# minime_2_1_1.net
KiCad netlist of a schematic drawn in EAGLE
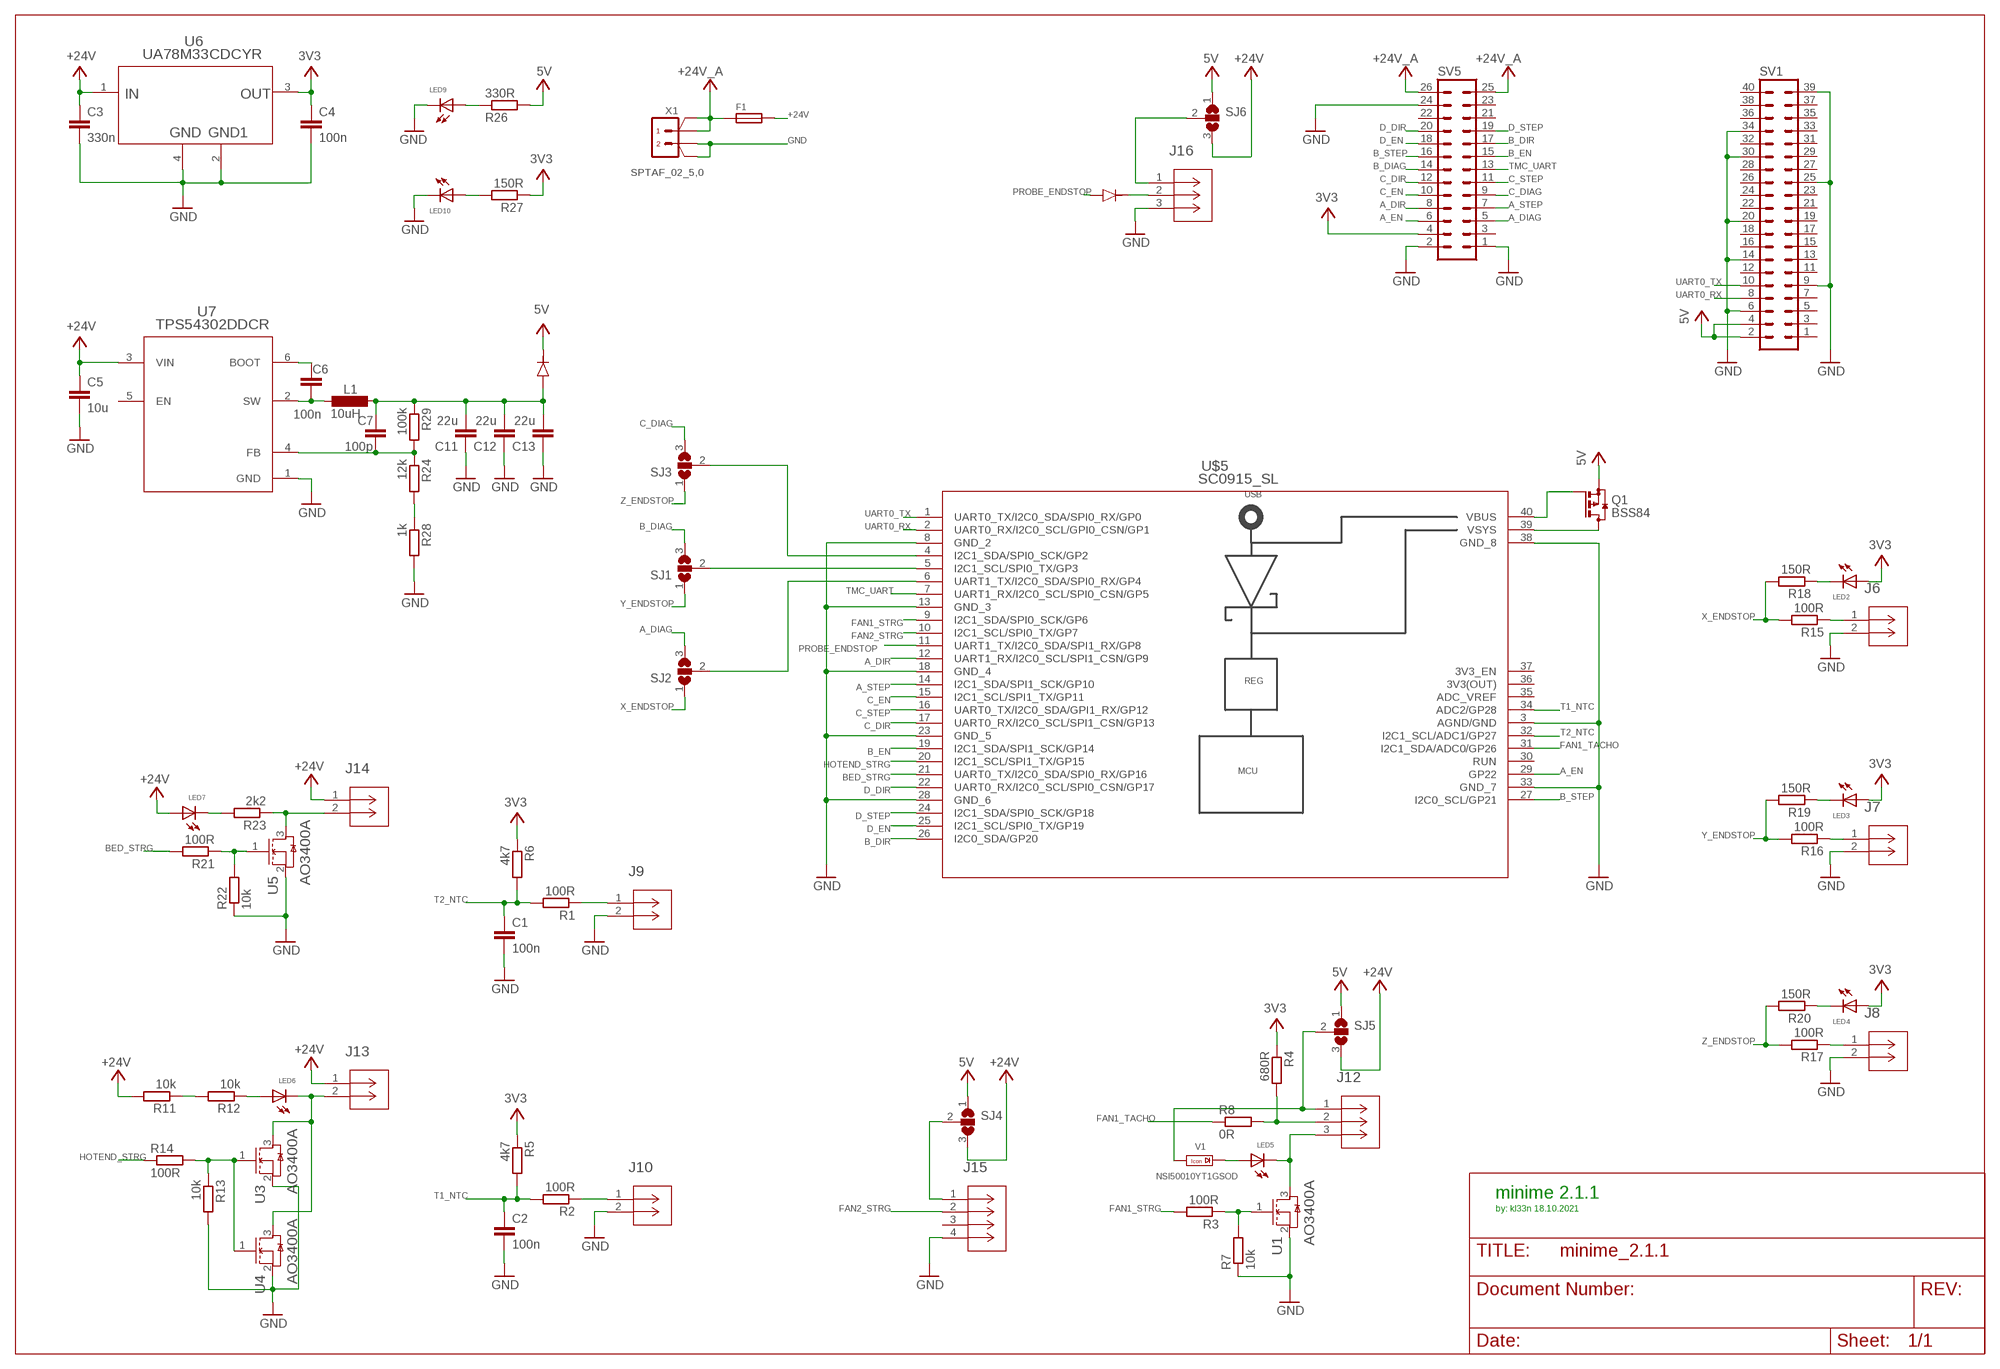
[diagram p0: schematic, sheet 1]

(export (version "E")
  (design (tool "Eeschema 10.0.6"))
  (components
    (comp (ref "C1")
      (value "100n")
      (footprint "eagle-import:C0603")
      (libsource (lib "eagle-import") (part "C-EUC0603"))
    )
    (comp (ref "C2")
      (value "100n")
      (footprint "eagle-import:C0603")
      (libsource (lib "eagle-import") (part "C-EUC0603"))
    )
    (comp (ref "C3")
      (value "330n")
      (footprint "eagle-import:C0603")
      (libsource (lib "eagle-import") (part "C-EUC0603"))
    )
    (comp (ref "C4")
      (value "100n")
      (footprint "eagle-import:C0603")
      (libsource (lib "eagle-import") (part "C-EUC0603"))
    )
    (comp (ref "C5")
      (value "10u")
      (footprint "eagle-import:C0603")
      (libsource (lib "eagle-import") (part "C-EUC0603"))
    )
    (comp (ref "C6")
      (value "100n")
      (footprint "eagle-import:C0603")
      (libsource (lib "eagle-import") (part "C-EUC0603"))
    )
    (comp (ref "C7")
      (value "100p")
      (footprint "eagle-import:C0603")
      (libsource (lib "eagle-import") (part "C-EUC0603"))
    )
    (comp (ref "C11")
      (value "22u")
      (footprint "eagle-import:C1210K")
      (libsource (lib "eagle-import") (part "C-EUC1210K"))
    )
    (comp (ref "C12")
      (value "22u")
      (footprint "eagle-import:C1210K")
      (libsource (lib "eagle-import") (part "C-EUC1210K"))
    )
    (comp (ref "C13")
      (value "22u")
      (footprint "eagle-import:C1210K")
      (libsource (lib "eagle-import") (part "C-EUC1210K"))
    )
    (comp (ref "CR1")
      (value "SS54")
      (footprint "eagle-import:DIODE_DO214AC")
      (fields
        (field (name "MANUFACTURER_PART_NUMBER") "SS14-E3/5AT")
        (field (name "COPYRIGHT") "Copyright (C) 2021 Ultra Librarian. All rights reserved.")
      )
      (libsource (lib "eagle-import") (part "SS14-E3/5AT"))
    )
    (comp (ref "CR2")
      (value "SS14")
      (footprint "eagle-import:DIODE_DO214AC")
      (fields
        (field (name "MANUFACTURER_PART_NUMBER") "SS14-E3/5AT")
        (field (name "COPYRIGHT") "Copyright (C) 2021 Ultra Librarian. All rights reserved.")
      )
      (libsource (lib "eagle-import") (part "SS14-E3/5AT"))
    )
    (comp (ref "F1")
      (value "FUSE/SERIE154")
      (footprint "eagle-import:FUSE_NANO-OMNI")
      (libsource (lib "eagle-import") (part "FUSE/SERIE154"))
    )
    (comp (ref "J6")
      (value "B2B-XH-A(LF)(SN)")
      (footprint "eagle-import:CONN_B2B-XH-A(LF)(SN)_JST")
      (fields (field (name "COPYRIGHT") "Copyright (C) 2018 Accelerated Designs. All rights reserved"))
      (libsource (lib "eagle-import") (part "B2B-XH-A(LF)(SN)"))
    )
    (comp (ref "J7")
      (value "B2B-XH-A(LF)(SN)")
      (footprint "eagle-import:CONN_B2B-XH-A(LF)(SN)_JST")
      (fields (field (name "COPYRIGHT") "Copyright (C) 2018 Accelerated Designs. All rights reserved"))
      (libsource (lib "eagle-import") (part "B2B-XH-A(LF)(SN)"))
    )
    (comp (ref "J8")
      (value "B2B-XH-A(LF)(SN)")
      (footprint "eagle-import:CONN_B2B-XH-A(LF)(SN)_JST")
      (fields (field (name "COPYRIGHT") "Copyright (C) 2018 Accelerated Designs. All rights reserved"))
      (libsource (lib "eagle-import") (part "B2B-XH-A(LF)(SN)"))
    )
    (comp (ref "J9")
      (value "B2B-XH-A(LF)(SN)")
      (footprint "eagle-import:CONN_B2B-XH-A(LF)(SN)_JST")
      (fields (field (name "COPYRIGHT") "Copyright (C) 2018 Accelerated Designs. All rights reserved"))
      (libsource (lib "eagle-import") (part "B2B-XH-A(LF)(SN)"))
    )
    (comp (ref "J10")
      (value "B2B-XH-A(LF)(SN)")
      (footprint "eagle-import:CONN_B2B-XH-A(LF)(SN)_JST")
      (fields (field (name "COPYRIGHT") "Copyright (C) 2018 Accelerated Designs. All rights reserved"))
      (libsource (lib "eagle-import") (part "B2B-XH-A(LF)(SN)"))
    )
    (comp (ref "J12")
      (value "B3B-XH-A(LF)(SN)")
      (footprint "eagle-import:CONN_B3B-XH-A_JST")
      (fields (field (name "COPYRIGHT") "Copyright (C) 2018 Accelerated Designs. All rights reserved"))
      (libsource (lib "eagle-import") (part "B3B-XH-A(LF)(SN)"))
    )
    (comp (ref "J13")
      (value "B2B-XH-A(LF)(SN)")
      (footprint "eagle-import:CONN_B2B-XH-A(LF)(SN)_JST")
      (fields (field (name "COPYRIGHT") "Copyright (C) 2018 Accelerated Designs. All rights reserved"))
      (libsource (lib "eagle-import") (part "B2B-XH-A(LF)(SN)"))
    )
    (comp (ref "J14")
      (value "B2B-XH-A(LF)(SN)")
      (footprint "eagle-import:CONN_B2B-XH-A(LF)(SN)_JST")
      (fields (field (name "COPYRIGHT") "Copyright (C) 2018 Accelerated Designs. All rights reserved"))
      (libsource (lib "eagle-import") (part "B2B-XH-A(LF)(SN)"))
    )
    (comp (ref "J15")
      (value "B4B-XH-AM(LF)(SN)")
      (footprint "eagle-import:CONN_B4B-XH-AM_JST")
      (fields (field (name "COPYRIGHT") "Copyright (C) 2018 Accelerated Designs. All rights reserved"))
      (libsource (lib "eagle-import") (part "B4B-XH-AM(LF)(SN)"))
    )
    (comp (ref "J16")
      (value "B3B-XH-A(LF)(SN)")
      (footprint "eagle-import:CONN_B3B-XH-A_JST")
      (fields (field (name "COPYRIGHT") "Copyright (C) 2018 Accelerated Designs. All rights reserved"))
      (libsource (lib "eagle-import") (part "B3B-XH-A(LF)(SN)"))
    )
    (comp (ref "L1")
      (value "10uH")
      (footprint "eagle-import:POWER-CHOKE_WE-TPC")
      (libsource (lib "eagle-import") (part "L-EUWE-TPC"))
    )
    (comp (ref "LED2")
      (value "LEDCHIP-LED0603")
      (footprint "eagle-import:CHIP-LED0603")
      (libsource (lib "eagle-import") (part "LEDCHIP-LED0603"))
    )
    (comp (ref "LED3")
      (value "LEDCHIP-LED0603")
      (footprint "eagle-import:CHIP-LED0603")
      (libsource (lib "eagle-import") (part "LEDCHIP-LED0603"))
    )
    (comp (ref "LED4")
      (value "LEDCHIP-LED0603")
      (footprint "eagle-import:CHIP-LED0603")
      (libsource (lib "eagle-import") (part "LEDCHIP-LED0603"))
    )
    (comp (ref "LED5")
      (value "LEDCHIP-LED0603")
      (footprint "eagle-import:CHIP-LED0603")
      (libsource (lib "eagle-import") (part "LEDCHIP-LED0603"))
    )
    (comp (ref "LED6")
      (value "LEDCHIP-LED0603")
      (footprint "eagle-import:CHIP-LED0603")
      (libsource (lib "eagle-import") (part "LEDCHIP-LED0603"))
    )
    (comp (ref "LED7")
      (value "LEDCHIP-LED0603")
      (footprint "eagle-import:CHIP-LED0603")
      (libsource (lib "eagle-import") (part "LEDCHIP-LED0603"))
    )
    (comp (ref "LED9")
      (value "LEDCHIP-LED0603")
      (footprint "eagle-import:CHIP-LED0603")
      (libsource (lib "eagle-import") (part "LEDCHIP-LED0603"))
    )
    (comp (ref "LED10")
      (value "LEDCHIP-LED0603")
      (footprint "eagle-import:CHIP-LED0603")
      (libsource (lib "eagle-import") (part "LEDCHIP-LED0603"))
    )
    (comp (ref "Q1")
      (value "BSS84")
      (footprint "eagle-import:SOT23")
      (libsource (lib "eagle-import") (part "BSS84"))
    )
    (comp (ref "R1")
      (value "100R")
      (footprint "eagle-import:R0603")
      (libsource (lib "eagle-import") (part "R-EU_R0603"))
    )
    (comp (ref "R2")
      (value "100R")
      (footprint "eagle-import:R0603")
      (libsource (lib "eagle-import") (part "R-EU_R0603"))
    )
    (comp (ref "R3")
      (value "100R")
      (footprint "eagle-import:R0603")
      (libsource (lib "eagle-import") (part "R-EU_R0603"))
    )
    (comp (ref "R4")
      (value "680R")
      (footprint "eagle-import:R0603")
      (libsource (lib "eagle-import") (part "R-EU_R0603"))
    )
    (comp (ref "R5")
      (value "4k7")
      (footprint "eagle-import:R0603")
      (libsource (lib "eagle-import") (part "R-EU_R0603"))
    )
    (comp (ref "R6")
      (value "4k7")
      (footprint "eagle-import:R0603")
      (libsource (lib "eagle-import") (part "R-EU_R0603"))
    )
    (comp (ref "R7")
      (value "10k")
      (footprint "eagle-import:R0603")
      (libsource (lib "eagle-import") (part "R-EU_R0603"))
    )
    (comp (ref "R8")
      (value "0R")
      (footprint "eagle-import:R0603")
      (libsource (lib "eagle-import") (part "R-EU_R0603"))
    )
    (comp (ref "R11")
      (value "10k")
      (footprint "eagle-import:R0603")
      (libsource (lib "eagle-import") (part "R-EU_R0603"))
    )
    (comp (ref "R12")
      (value "10k")
      (footprint "eagle-import:R0603")
      (libsource (lib "eagle-import") (part "R-EU_R0603"))
    )
    (comp (ref "R13")
      (value "10k")
      (footprint "eagle-import:R0603")
      (libsource (lib "eagle-import") (part "R-EU_R0603"))
    )
    (comp (ref "R14")
      (value "100R")
      (footprint "eagle-import:R0603")
      (libsource (lib "eagle-import") (part "R-EU_R0603"))
    )
    (comp (ref "R15")
      (value "100R")
      (footprint "eagle-import:R0603")
      (libsource (lib "eagle-import") (part "R-EU_R0603"))
    )
    (comp (ref "R16")
      (value "100R")
      (footprint "eagle-import:R0603")
      (libsource (lib "eagle-import") (part "R-EU_R0603"))
    )
    (comp (ref "R17")
      (value "100R")
      (footprint "eagle-import:R0603")
      (libsource (lib "eagle-import") (part "R-EU_R0603"))
    )
    (comp (ref "R18")
      (value "150R")
      (footprint "eagle-import:R0603")
      (libsource (lib "eagle-import") (part "R-EU_R0603"))
    )
    (comp (ref "R19")
      (value "150R")
      (footprint "eagle-import:R0603")
      (libsource (lib "eagle-import") (part "R-EU_R0603"))
    )
    (comp (ref "R20")
      (value "150R")
      (footprint "eagle-import:R0603")
      (libsource (lib "eagle-import") (part "R-EU_R0603"))
    )
    (comp (ref "R21")
      (value "100R")
      (footprint "eagle-import:R0603")
      (libsource (lib "eagle-import") (part "R-EU_R0603"))
    )
    (comp (ref "R22")
      (value "10k")
      (footprint "eagle-import:R0603")
      (libsource (lib "eagle-import") (part "R-EU_R0603"))
    )
    (comp (ref "R23")
      (value "2k2")
      (footprint "eagle-import:R0603")
      (libsource (lib "eagle-import") (part "R-EU_R0603"))
    )
    (comp (ref "R24")
      (value "12k")
      (footprint "eagle-import:R0603")
      (libsource (lib "eagle-import") (part "R-EU_R0603"))
    )
    (comp (ref "R26")
      (value "330R")
      (footprint "eagle-import:R0603")
      (libsource (lib "eagle-import") (part "R-EU_R0603"))
    )
    (comp (ref "R27")
      (value "150R")
      (footprint "eagle-import:R0603")
      (libsource (lib "eagle-import") (part "R-EU_R0603"))
    )
    (comp (ref "R28")
      (value "1k")
      (footprint "eagle-import:R0603")
      (libsource (lib "eagle-import") (part "R-EU_R0603"))
    )
    (comp (ref "R29")
      (value "100k")
      (footprint "eagle-import:R0603")
      (libsource (lib "eagle-import") (part "R-EU_R0603"))
    )
    (comp (ref "SJ1")
      (value "SJ2W")
      (footprint "eagle-import:SJ_2")
      (libsource (lib "eagle-import") (part "SJ2W"))
    )
    (comp (ref "SJ2")
      (value "SJ2W")
      (footprint "eagle-import:SJ_2")
      (libsource (lib "eagle-import") (part "SJ2W"))
    )
    (comp (ref "SJ3")
      (value "SJ2W")
      (footprint "eagle-import:SJ_2")
      (libsource (lib "eagle-import") (part "SJ2W"))
    )
    (comp (ref "SJ4")
      (value "SJ2W")
      (footprint "eagle-import:SJ_2")
      (libsource (lib "eagle-import") (part "SJ2W"))
    )
    (comp (ref "SJ5")
      (value "SJ2W")
      (footprint "eagle-import:SJ_2")
      (libsource (lib "eagle-import") (part "SJ2W"))
    )
    (comp (ref "SJ6")
      (value "SJ2W")
      (footprint "eagle-import:SJ_2")
      (libsource (lib "eagle-import") (part "SJ2W"))
    )
    (comp (ref "SV1")
      (value "MA20-2")
      (footprint "eagle-import:MA20-2")
      (libsource (lib "eagle-import") (part "MA20-2"))
    )
    (comp (ref "SV5")
      (value "MA13-2")
      (footprint "eagle-import:MA13-2")
      (libsource (lib "eagle-import") (part "MA13-2"))
    )
    (comp (ref "U$5")
      (value "SC0915_SL")
      (footprint "eagle-import:STIFTLEISTE")
      (libsource (lib "eagle-import") (part "SC0915_SL"))
    )
    (comp (ref "U1")
      (value "AO3400A")
      (footprint "eagle-import:SOT-23-3L_AOS")
      (fields (field (name "COPYRIGHT") "Copyright (C) 2018 Accelerated Designs. All rights reserved"))
      (libsource (lib "eagle-import") (part "AO3400A"))
    )
    (comp (ref "U3")
      (value "AO3400A")
      (footprint "eagle-import:SOT-23-3L_AOS")
      (fields (field (name "COPYRIGHT") "Copyright (C) 2018 Accelerated Designs. All rights reserved"))
      (libsource (lib "eagle-import") (part "AO3400A"))
    )
    (comp (ref "U4")
      (value "AO3400A")
      (footprint "eagle-import:SOT-23-3L_AOS")
      (fields (field (name "COPYRIGHT") "Copyright (C) 2018 Accelerated Designs. All rights reserved"))
      (libsource (lib "eagle-import") (part "AO3400A"))
    )
    (comp (ref "U5")
      (value "AO3400A")
      (footprint "eagle-import:SOT-23-3L_AOS")
      (fields (field (name "COPYRIGHT") "Copyright (C) 2018 Accelerated Designs. All rights reserved"))
      (libsource (lib "eagle-import") (part "AO3400A"))
    )
    (comp (ref "U6")
      (value "UA78M33CDCYR")
      (footprint "eagle-import:DCY0004A_N")
      (fields (field (name "COPYRIGHT") "Copyright (C) 2021 Ultra Librarian. All rights reserved."))
      (libsource (lib "eagle-import") (part "UA78M33CDCYR"))
    )
    (comp (ref "U7")
      (value "TPS54302DDCR")
      (footprint "eagle-import:DDC0006A_N")
      (fields (field (name "COPYRIGHT") "Copyright (C) 2021 Ultra Librarian. All rights reserved."))
      (libsource (lib "eagle-import") (part "TPS54302DDCR"))
    )
    (comp (ref "V1")
      (value "NSI50010YT1GSOD")
      (footprint "eagle-import:SOD123")
      (libsource (lib "eagle-import") (part "NSI50010YT1GSOD"))
    )
    (comp (ref "X1")
      (value "SPTAF_02_5,0")
      (footprint "eagle-import:5-2")
      (libsource (lib "eagle-import") (part "SPTAF_02_5,0"))
    )
  )
  (nets
    (net (code "1") (name "+24V") (class "Default")
      (node (ref "C3") (pin "1") (pinfunction "1_1") (pintype "passive"))
      (node (ref "C5") (pin "1") (pinfunction "1_1") (pintype "passive"))
      (node (ref "F1") (pin "2") (pinfunction "2_2") (pintype "passive"))
      (node (ref "J13") (pin "1") (pinfunction "1_1") (pintype "passive"))
      (node (ref "J14") (pin "1") (pinfunction "1_1") (pintype "passive"))
      (node (ref "LED7") (pin "A") (pinfunction "A_A") (pintype "passive"))
      (node (ref "R11") (pin "2") (pinfunction "2_2") (pintype "passive"))
      (node (ref "SJ4") (pin "3") (pinfunction "3_3") (pintype "passive"))
      (node (ref "SJ5") (pin "3") (pinfunction "3_3") (pintype "passive"))
      (node (ref "SJ6") (pin "3") (pinfunction "3_3") (pintype "passive"))
      (node (ref "U6") (pin "1") (pinfunction "INPUT_1") (pintype "power_in"))
      (node (ref "U7") (pin "3") (pinfunction "VIN_3") (pintype "power_in"))
    )
    (net (code "2") (name "+24V_A") (class "Default")
      (node (ref "F1") (pin "1") (pinfunction "1_1") (pintype "passive"))
      (node (ref "SV5") (pin "25") (pinfunction "25_25") (pintype "passive"))
      (node (ref "SV5") (pin "26") (pinfunction "26_26") (pintype "passive"))
      (node (ref "X1") (pin "1") (pinfunction "1_1") (pintype "passive"))
      (node (ref "X1") (pin "1A") (pinfunction "1A_1A") (pintype "passive"))
    )
    (net (code "3") (name "/3V3_EN") (class "Default")
      (node (ref "U$5") (pin "37") (pinfunction "3V3_EN_37") (pintype "power_in"))
    )
    (net (code "4") (name "/ADC_VREF") (class "Default")
      (node (ref "U$5") (pin "35") (pinfunction "ADC_VREF_35") (pintype "power_in"))
    )
    (net (code "5") (name "/A_DIAG") (class "Default")
      (node (ref "SJ2") (pin "3") (pinfunction "3_3") (pintype "passive"))
      (node (ref "SV5") (pin "5") (pinfunction "5_5") (pintype "passive"))
    )
    (net (code "6") (name "/A_DIR") (class "Default")
      (node (ref "SV5") (pin "8") (pinfunction "8_8") (pintype "passive"))
      (node (ref "U$5") (pin "12") (pinfunction "UART1_RX/I2C0_SCL/SPI1_CSN/GP9_12") (pintype "bidirectional"))
    )
    (net (code "7") (name "/A_EN") (class "Default")
      (node (ref "SV5") (pin "6") (pinfunction "6_6") (pintype "passive"))
      (node (ref "U$5") (pin "29") (pinfunction "GP22_29") (pintype "bidirectional"))
    )
    (net (code "8") (name "/A_STEP") (class "Default")
      (node (ref "SV5") (pin "7") (pinfunction "7_7") (pintype "passive"))
      (node (ref "U$5") (pin "14") (pinfunction "I2C1_SDA/SPI1_SCK/GP10_14") (pintype "bidirectional"))
    )
    (net (code "9") (name "/BED_STRG") (class "Default")
      (node (ref "R21") (pin "2") (pinfunction "2_2") (pintype "passive"))
      (node (ref "U$5") (pin "21") (pinfunction "UART0_TX/I2C0_SDA/SPI0_RX/GP16_21") (pintype "bidirectional"))
    )
    (net (code "10") (name "/B_DIAG") (class "Default")
      (node (ref "SJ1") (pin "3") (pinfunction "3_3") (pintype "passive"))
      (node (ref "SV5") (pin "14") (pinfunction "14_14") (pintype "passive"))
    )
    (net (code "11") (name "/B_DIR") (class "Default")
      (node (ref "SV5") (pin "17") (pinfunction "17_17") (pintype "passive"))
      (node (ref "U$5") (pin "26") (pinfunction "I2C0_SDA/GP20_26") (pintype "bidirectional"))
    )
    (net (code "12") (name "/B_EN") (class "Default")
      (node (ref "SV5") (pin "15") (pinfunction "15_15") (pintype "passive"))
      (node (ref "U$5") (pin "19") (pinfunction "I2C1_SDA/SPI1_SCK/GP14_19") (pintype "bidirectional"))
    )
    (net (code "13") (name "/B_STEP") (class "Default")
      (node (ref "SV5") (pin "16") (pinfunction "16_16") (pintype "passive"))
      (node (ref "U$5") (pin "27") (pinfunction "I2C0_SCL/GP21_27") (pintype "bidirectional"))
    )
    (net (code "14") (name "/C_DIAG") (class "Default")
      (node (ref "SJ3") (pin "3") (pinfunction "3_3") (pintype "passive"))
      (node (ref "SV5") (pin "9") (pinfunction "9_9") (pintype "passive"))
    )
    (net (code "15") (name "/C_DIR") (class "Default")
      (node (ref "SV5") (pin "12") (pinfunction "12_12") (pintype "passive"))
      (node (ref "U$5") (pin "17") (pinfunction "UART0_RX/I2C0_SCL/SPI1_CSN/GP13_17") (pintype "bidirectional"))
    )
    (net (code "16") (name "/C_EN") (class "Default")
      (node (ref "SV5") (pin "10") (pinfunction "10_10") (pintype "passive"))
      (node (ref "U$5") (pin "15") (pinfunction "I2C1_SCL/SPI1_TX/GP11_15") (pintype "bidirectional"))
    )
    (net (code "17") (name "/C_STEP") (class "Default")
      (node (ref "SV5") (pin "11") (pinfunction "11_11") (pintype "passive"))
      (node (ref "U$5") (pin "16") (pinfunction "UART0_TX/I2C0_SDA/GPI1_RX/GP12_16") (pintype "bidirectional"))
    )
    (net (code "18") (name "/D_DIR") (class "Default")
      (node (ref "SV5") (pin "20") (pinfunction "20_20") (pintype "passive"))
      (node (ref "U$5") (pin "22") (pinfunction "UART0_RX/I2C0_SCL/SPI0_CSN/GP17_22") (pintype "bidirectional"))
    )
    (net (code "19") (name "/D_EN") (class "Default")
      (node (ref "SV5") (pin "18") (pinfunction "18_18") (pintype "passive"))
      (node (ref "U$5") (pin "25") (pinfunction "I2C1_SCL/SPI0_TX/GP19_25") (pintype "bidirectional"))
    )
    (net (code "20") (name "/D_STEP") (class "Default")
      (node (ref "SV5") (pin "19") (pinfunction "19_19") (pintype "passive"))
      (node (ref "U$5") (pin "24") (pinfunction "I2C1_SDA/SPI0_SCK/GP18_24") (pintype "bidirectional"))
    )
    (net (code "21") (name "/FAN1_STRG") (class "Default")
      (node (ref "R3") (pin "2") (pinfunction "2_2") (pintype "passive"))
      (node (ref "U$5") (pin "9") (pinfunction "I2C1_SDA/SPI0_SCK/GP6_9") (pintype "bidirectional"))
    )
    (net (code "22") (name "/FAN1_TACHO") (class "Default")
      (node (ref "R8") (pin "1") (pinfunction "1_1") (pintype "passive"))
      (node (ref "U$5") (pin "31") (pinfunction "I2C1_SDA/ADC0/GP26_31") (pintype "bidirectional"))
    )
    (net (code "23") (name "/FAN2_STRG") (class "Default")
      (node (ref "J15") (pin "2") (pinfunction "2_2") (pintype "passive"))
      (node (ref "U$5") (pin "10") (pinfunction "I2C1_SCL/SPI0_TX/GP7_10") (pintype "bidirectional"))
    )
    (net (code "24") (name "/HOTEND_STRG") (class "Default")
      (node (ref "R14") (pin "1") (pinfunction "1_1") (pintype "passive"))
      (node (ref "U$5") (pin "20") (pinfunction "I2C1_SCL/SPI1_TX/GP15_20") (pintype "bidirectional"))
    )
    (net (code "25") (name "/PROBE_ENDSTOP") (class "Default")
      (node (ref "CR2") (pin "2") (pinfunction "2_2") (pintype "passive"))
      (node (ref "U$5") (pin "11") (pinfunction "UART1_TX/I2C0_SDA/SPI1_RX/GP8_11") (pintype "bidirectional"))
    )
    (net (code "26") (name "/T1_NTC") (class "Default")
      (node (ref "C2") (pin "1") (pinfunction "1_1") (pintype "passive"))
      (node (ref "R2") (pin "2") (pinfunction "2_2") (pintype "passive"))
      (node (ref "R5") (pin "2") (pinfunction "2_2") (pintype "passive"))
      (node (ref "U$5") (pin "34") (pinfunction "ADC2/GP28_34") (pintype "bidirectional"))
    )
    (net (code "27") (name "/T2_NTC") (class "Default")
      (node (ref "C1") (pin "1") (pinfunction "1_1") (pintype "passive"))
      (node (ref "R1") (pin "2") (pinfunction "2_2") (pintype "passive"))
      (node (ref "R6") (pin "2") (pinfunction "2_2") (pintype "passive"))
      (node (ref "U$5") (pin "32") (pinfunction "I2C1_SCL/ADC1/GP27_32") (pintype "bidirectional"))
    )
    (net (code "28") (name "/TMC_UART") (class "Default")
      (node (ref "SV5") (pin "13") (pinfunction "13_13") (pintype "passive"))
      (node (ref "U$5") (pin "7") (pinfunction "UART1_RX/I2C0_SCL/SPI0_CSN/GP5_7") (pintype "bidirectional"))
    )
    (net (code "29") (name "/UART0_RX") (class "Default")
      (node (ref "SV1") (pin "8") (pinfunction "8_8") (pintype "passive"))
      (node (ref "U$5") (pin "2") (pinfunction "UART0_RX/I2C0_SCL/GPI0_CSN/GP1_2") (pintype "bidirectional"))
    )
    (net (code "30") (name "/UART0_TX") (class "Default")
      (node (ref "SV1") (pin "10") (pinfunction "10_10") (pintype "passive"))
      (node (ref "U$5") (pin "1") (pinfunction "UART0_TX/I2C0_SDA/SPI0_RX/GP0_1") (pintype "bidirectional"))
    )
    (net (code "31") (name "/X_ENDSTOP") (class "Default")
      (node (ref "R15") (pin "2") (pinfunction "2_2") (pintype "passive"))
      (node (ref "R18") (pin "2") (pinfunction "2_2") (pintype "passive"))
      (node (ref "SJ2") (pin "1") (pinfunction "1_1") (pintype "passive"))
    )
    (net (code "32") (name "/Y_ENDSTOP") (class "Default")
      (node (ref "R16") (pin "2") (pinfunction "2_2") (pintype "passive"))
      (node (ref "R19") (pin "2") (pinfunction "2_2") (pintype "passive"))
      (node (ref "SJ1") (pin "1") (pinfunction "1_1") (pintype "passive"))
    )
    (net (code "33") (name "/Z_ENDSTOP") (class "Default")
      (node (ref "R17") (pin "2") (pinfunction "2_2") (pintype "passive"))
      (node (ref "R20") (pin "2") (pinfunction "2_2") (pintype "passive"))
      (node (ref "SJ3") (pin "1") (pinfunction "1_1") (pintype "passive"))
    )
    (net (code "34") (name "3V3") (class "Default")
      (node (ref "C4") (pin "1") (pinfunction "1_1") (pintype "passive"))
      (node (ref "LED2") (pin "A") (pinfunction "A_A") (pintype "passive"))
      (node (ref "LED3") (pin "A") (pinfunction "A_A") (pintype "passive"))
      (node (ref "LED4") (pin "A") (pinfunction "A_A") (pintype "passive"))
      (node (ref "R27") (pin "1") (pinfunction "1_1") (pintype "passive"))
      (node (ref "R4") (pin "1") (pinfunction "1_1") (pintype "passive"))
      (node (ref "R5") (pin "1") (pinfunction "1_1") (pintype "passive"))
      (node (ref "R6") (pin "1") (pinfunction "1_1") (pintype "passive"))
      (node (ref "SV5") (pin "4") (pinfunction "4_4") (pintype "passive"))
      (node (ref "U6") (pin "3") (pinfunction "OUTPUT_3") (pintype "power_in"))
    )
    (net (code "35") (name "5V") (class "Default")
      (node (ref "CR1") (pin "1") (pinfunction "1_1") (pintype "passive"))
      (node (ref "Q1") (pin "2") (pinfunction "S_2") (pintype "passive"))
      (node (ref "R26") (pin "2") (pinfunction "2_2") (pintype "passive"))
      (node (ref "SJ4") (pin "1") (pinfunction "1_1") (pintype "passive"))
      (node (ref "SJ5") (pin "1") (pinfunction "1_1") (pintype "passive"))
      (node (ref "SJ6") (pin "1") (pinfunction "1_1") (pintype "passive"))
      (node (ref "SV1") (pin "2") (pinfunction "2_2") (pintype "passive"))
      (node (ref "SV1") (pin "4") (pinfunction "4_4") (pintype "passive"))
    )
    (net (code "36") (name "GND") (class "Default")
      (node (ref "C1") (pin "2") (pinfunction "2_2") (pintype "passive"))
      (node (ref "C11") (pin "1") (pinfunction "1_1") (pintype "passive"))
      (node (ref "C12") (pin "1") (pinfunction "1_1") (pintype "passive"))
      (node (ref "C13") (pin "1") (pinfunction "1_1") (pintype "passive"))
      (node (ref "C2") (pin "2") (pinfunction "2_2") (pintype "passive"))
      (node (ref "C3") (pin "2") (pinfunction "2_2") (pintype "passive"))
      (node (ref "C4") (pin "2") (pinfunction "2_2") (pintype "passive"))
      (node (ref "C5") (pin "2") (pinfunction "2_2") (pintype "passive"))
      (node (ref "J10") (pin "2") (pinfunction "2_2") (pintype "passive"))
      (node (ref "J15") (pin "4") (pinfunction "4_4") (pintype "passive"))
      (node (ref "J16") (pin "3") (pinfunction "3_3") (pintype "passive"))
      (node (ref "J6") (pin "2") (pinfunction "2_2") (pintype "passive"))
      (node (ref "J7") (pin "2") (pinfunction "2_2") (pintype "passive"))
      (node (ref "J8") (pin "2") (pinfunction "2_2") (pintype "passive"))
      (node (ref "J9") (pin "2") (pinfunction "2_2") (pintype "passive"))
      (node (ref "LED10") (pin "C") (pinfunction "C_C") (pintype "passive"))
      (node (ref "LED9") (pin "C") (pinfunction "C_C") (pintype "passive"))
      (node (ref "R13") (pin "2") (pinfunction "2_2") (pintype "passive"))
      (node (ref "R22") (pin "1") (pinfunction "1_1") (pintype "passive"))
      (node (ref "R28") (pin "2") (pinfunction "2_2") (pintype "passive"))
      (node (ref "R7") (pin "1") (pinfunction "1_1") (pintype "passive"))
      (node (ref "SV1") (pin "14") (pinfunction "14_14") (pintype "passive"))
      (node (ref "SV1") (pin "20") (pinfunction "20_20") (pintype "passive"))
      (node (ref "SV1") (pin "25") (pinfunction "25_25") (pintype "passive"))
      (node (ref "SV1") (pin "30") (pinfunction "30_30") (pintype "passive"))
      (node (ref "SV1") (pin "34") (pinfunction "34_34") (pintype "passive"))
      (node (ref "SV1") (pin "39") (pinfunction "39_39") (pintype "passive"))
      (node (ref "SV1") (pin "6") (pinfunction "6_6") (pintype "passive"))
      (node (ref "SV1") (pin "9") (pinfunction "9_9") (pintype "passive"))
      (node (ref "SV5") (pin "1") (pinfunction "1_1") (pintype "passive"))
      (node (ref "SV5") (pin "2") (pinfunction "2_2") (pintype "passive"))
      (node (ref "SV5") (pin "24") (pinfunction "24_24") (pintype "passive"))
      (node (ref "U$5") (pin "13") (pinfunction "GND_3_13") (pintype "passive"))
      (node (ref "U$5") (pin "18") (pinfunction "GND_4_18") (pintype "passive"))
      (node (ref "U$5") (pin "23") (pinfunction "GND_5_23") (pintype "passive"))
      (node (ref "U$5") (pin "28") (pinfunction "GND_6_28") (pintype "passive"))
      (node (ref "U$5") (pin "3") (pinfunction "AGND/GND_3") (pintype "passive"))
      (node (ref "U$5") (pin "33") (pinfunction "GND_7_33") (pintype "passive"))
      (node (ref "U$5") (pin "38") (pinfunction "GND_8_38") (pintype "passive"))
      (node (ref "U$5") (pin "8") (pinfunction "GND_2_8") (pintype "passive"))
      (node (ref "U1") (pin "2") (pinfunction "S_2") (pintype "passive"))
      (node (ref "U3") (pin "2") (pinfunction "S_2") (pintype "passive"))
      (node (ref "U4") (pin "2") (pinfunction "S_2") (pintype "passive"))
      (node (ref "U5") (pin "2") (pinfunction "S_2") (pintype "passive"))
      (node (ref "U6") (pin "2") (pinfunction "COMMON_2_2") (pintype "power_in"))
      (node (ref "U6") (pin "4") (pinfunction "COMMON_4") (pintype "power_in"))
      (node (ref "U7") (pin "1") (pinfunction "GND_1") (pintype "power_in"))
      (node (ref "X1") (pin "2") (pinfunction "2_2") (pintype "passive"))
      (node (ref "X1") (pin "2A") (pinfunction "2A_2A") (pintype "passive"))
    )
    (net (code "37") (name "Net-(C11-Pad2)") (class "Default")
      (node (ref "C11") (pin "2") (pinfunction "2_2") (pintype "passive"))
      (node (ref "C12") (pin "2") (pinfunction "2_2") (pintype "passive"))
      (node (ref "C13") (pin "2") (pinfunction "2_2") (pintype "passive"))
      (node (ref "C7") (pin "1") (pinfunction "1_1") (pintype "passive"))
      (node (ref "CR1") (pin "2") (pinfunction "2_2") (pintype "passive"))
      (node (ref "L1") (pin "1") (pinfunction "1_1") (pintype "passive"))
      (node (ref "R29") (pin "1") (pinfunction "1_1") (pintype "passive"))
    )
    (net (code "38") (name "Net-(CR2-Pad1)") (class "Default")
      (node (ref "CR2") (pin "1") (pinfunction "1_1") (pintype "passive"))
      (node (ref "J16") (pin "2") (pinfunction "2_2") (pintype "passive"))
    )
    (net (code "39") (name "Net-(J6-Pad1)") (class "Default")
      (node (ref "J6") (pin "1") (pinfunction "1_1") (pintype "passive"))
      (node (ref "R15") (pin "1") (pinfunction "1_1") (pintype "passive"))
    )
    (net (code "40") (name "Net-(J7-Pad1)") (class "Default")
      (node (ref "J7") (pin "1") (pinfunction "1_1") (pintype "passive"))
      (node (ref "R16") (pin "1") (pinfunction "1_1") (pintype "passive"))
    )
    (net (code "41") (name "Net-(J8-Pad1)") (class "Default")
      (node (ref "J8") (pin "1") (pinfunction "1_1") (pintype "passive"))
      (node (ref "R17") (pin "1") (pinfunction "1_1") (pintype "passive"))
    )
    (net (code "42") (name "Net-(J9-Pad1)") (class "Default")
      (node (ref "J9") (pin "1") (pinfunction "1_1") (pintype "passive"))
      (node (ref "R1") (pin "1") (pinfunction "1_1") (pintype "passive"))
    )
    (net (code "43") (name "Net-(J10-Pad1)") (class "Default")
      (node (ref "J10") (pin "1") (pinfunction "1_1") (pintype "passive"))
      (node (ref "R2") (pin "1") (pinfunction "1_1") (pintype "passive"))
    )
    (net (code "44") (name "Net-(J12-Pad1)") (class "Default")
      (node (ref "J12") (pin "1") (pinfunction "1_1") (pintype "passive"))
      (node (ref "SJ5") (pin "2") (pinfunction "2_2") (pintype "passive"))
      (node (ref "V1") (pin "A") (pinfunction "A_A") (pintype "bidirectional"))
    )
    (net (code "45") (name "Net-(J12-Pad2)") (class "Default")
      (node (ref "J12") (pin "2") (pinfunction "2_2") (pintype "passive"))
      (node (ref "R4") (pin "2") (pinfunction "2_2") (pintype "passive"))
      (node (ref "R8") (pin "2") (pinfunction "2_2") (pintype "passive"))
    )
    (net (code "46") (name "Net-(J15-Pad1)") (class "Default")
      (node (ref "J15") (pin "1") (pinfunction "1_1") (pintype "passive"))
      (node (ref "SJ4") (pin "2") (pinfunction "2_2") (pintype "passive"))
    )
    (net (code "47") (name "Net-(J16-Pad1)") (class "Default")
      (node (ref "J16") (pin "1") (pinfunction "1_1") (pintype "passive"))
      (node (ref "SJ6") (pin "2") (pinfunction "2_2") (pintype "passive"))
    )
    (net (code "48") (name "Net-(LED2-PadC)") (class "Default")
      (node (ref "LED2") (pin "C") (pinfunction "C_C") (pintype "passive"))
      (node (ref "R18") (pin "1") (pinfunction "1_1") (pintype "passive"))
    )
    (net (code "49") (name "Net-(LED3-PadC)") (class "Default")
      (node (ref "LED3") (pin "C") (pinfunction "C_C") (pintype "passive"))
      (node (ref "R19") (pin "1") (pinfunction "1_1") (pintype "passive"))
    )
    (net (code "50") (name "Net-(LED4-PadC)") (class "Default")
      (node (ref "LED4") (pin "C") (pinfunction "C_C") (pintype "passive"))
      (node (ref "R20") (pin "1") (pinfunction "1_1") (pintype "passive"))
    )
    (net (code "51") (name "Net-(LED6-PadA)") (class "Default")
      (node (ref "LED6") (pin "A") (pinfunction "A_A") (pintype "passive"))
      (node (ref "R12") (pin "1") (pinfunction "1_1") (pintype "passive"))
    )
    (net (code "52") (name "Net-(LED7-PadC)") (class "Default")
      (node (ref "LED7") (pin "C") (pinfunction "C_C") (pintype "passive"))
      (node (ref "R23") (pin "2") (pinfunction "2_2") (pintype "passive"))
    )
    (net (code "53") (name "Net-(LED9-PadA)") (class "Default")
      (node (ref "LED9") (pin "A") (pinfunction "A_A") (pintype "passive"))
      (node (ref "R26") (pin "1") (pinfunction "1_1") (pintype "passive"))
    )
    (net (code "54") (name "Net-(LED10-PadA)") (class "Default")
      (node (ref "LED10") (pin "A") (pinfunction "A_A") (pintype "passive"))
      (node (ref "R27") (pin "2") (pinfunction "2_2") (pintype "passive"))
    )
    (net (code "55") (name "Net-(Q1-D)") (class "Default")
      (node (ref "Q1") (pin "3") (pinfunction "D_3") (pintype "passive"))
      (node (ref "U$5") (pin "39") (pinfunction "VSYS_39") (pintype "power_in"))
    )
    (net (code "56") (name "Net-(Q1-G)") (class "Default")
      (node (ref "Q1") (pin "1") (pinfunction "G_1") (pintype "passive"))
      (node (ref "U$5") (pin "40") (pinfunction "VBUS_40") (pintype "power_in"))
    )
    (net (code "57") (name "Net-(R11-Pad1)") (class "Default")
      (node (ref "R11") (pin "1") (pinfunction "1_1") (pintype "passive"))
      (node (ref "R12") (pin "2") (pinfunction "2_2") (pintype "passive"))
    )
    (net (code "58") (name "Net-(R24-Pad2)") (class "Default")
      (node (ref "R24") (pin "2") (pinfunction "2_2") (pintype "passive"))
      (node (ref "R28") (pin "1") (pinfunction "1_1") (pintype "passive"))
    )
    (net (code "59") (name "Net-(U$5-I2C1_SCL{slash}SPI0_TX{slash}GP3)") (class "Default")
      (node (ref "SJ1") (pin "2") (pinfunction "2_2") (pintype "passive"))
      (node (ref "U$5") (pin "5") (pinfunction "I2C1_SCL/SPI0_TX/GP3_5") (pintype "bidirectional"))
    )
    (net (code "60") (name "Net-(U$5-I2C1_SDA{slash}SPI0_SCK{slash}GP2)") (class "Default")
      (node (ref "SJ3") (pin "2") (pinfunction "2_2") (pintype "passive"))
      (node (ref "U$5") (pin "4") (pinfunction "I2C1_SDA/SPI0_SCK/GP2_4") (pintype "bidirectional"))
    )
    (net (code "61") (name "Net-(U$5-UART1_TX{slash}I2C0_SDA{slash}SPI0_RX{slash}GP4)") (class "Default")
      (node (ref "SJ2") (pin "2") (pinfunction "2_2") (pintype "passive"))
      (node (ref "U$5") (pin "6") (pinfunction "UART1_TX/I2C0_SDA/SPI0_RX/GP4_6") (pintype "bidirectional"))
    )
    (net (code "62") (name "Net-(U1-D)") (class "Default")
      (node (ref "J12") (pin "3") (pinfunction "3_3") (pintype "passive"))
      (node (ref "LED5") (pin "C") (pinfunction "C_C") (pintype "passive"))
      (node (ref "U1") (pin "3") (pinfunction "D_3") (pintype "passive"))
    )
    (net (code "63") (name "Net-(U1-G)") (class "Default")
      (node (ref "R3") (pin "1") (pinfunction "1_1") (pintype "passive"))
      (node (ref "R7") (pin "2") (pinfunction "2_2") (pintype "passive"))
      (node (ref "U1") (pin "1") (pinfunction "G_1") (pintype "passive"))
    )
    (net (code "64") (name "Net-(U3-D)") (class "Default")
      (node (ref "J13") (pin "2") (pinfunction "2_2") (pintype "passive"))
      (node (ref "LED6") (pin "C") (pinfunction "C_C") (pintype "passive"))
      (node (ref "U3") (pin "3") (pinfunction "D_3") (pintype "passive"))
      (node (ref "U4") (pin "3") (pinfunction "D_3") (pintype "passive"))
    )
    (net (code "65") (name "Net-(U3-G)") (class "Default")
      (node (ref "R13") (pin "1") (pinfunction "1_1") (pintype "passive"))
      (node (ref "R14") (pin "2") (pinfunction "2_2") (pintype "passive"))
      (node (ref "U3") (pin "1") (pinfunction "G_1") (pintype "passive"))
      (node (ref "U4") (pin "1") (pinfunction "G_1") (pintype "passive"))
    )
    (net (code "66") (name "Net-(U5-D)") (class "Default")
      (node (ref "J14") (pin "2") (pinfunction "2_2") (pintype "passive"))
      (node (ref "R23") (pin "1") (pinfunction "1_1") (pintype "passive"))
      (node (ref "U5") (pin "3") (pinfunction "D_3") (pintype "passive"))
    )
    (net (code "67") (name "Net-(U5-G)") (class "Default")
      (node (ref "R21") (pin "1") (pinfunction "1_1") (pintype "passive"))
      (node (ref "R22") (pin "2") (pinfunction "2_2") (pintype "passive"))
      (node (ref "U5") (pin "1") (pinfunction "G_1") (pintype "passive"))
    )
    (net (code "68") (name "Net-(U7-BOOT)") (class "Default")
      (node (ref "C6") (pin "1") (pinfunction "1_1") (pintype "passive"))
      (node (ref "U7") (pin "6") (pinfunction "BOOT_6") (pintype "power_in"))
    )
    (net (code "69") (name "Net-(U7-FB)") (class "Default")
      (node (ref "C7") (pin "2") (pinfunction "2_2") (pintype "passive"))
      (node (ref "R24") (pin "1") (pinfunction "1_1") (pintype "passive"))
      (node (ref "R29") (pin "2") (pinfunction "2_2") (pintype "passive"))
      (node (ref "U7") (pin "4") (pinfunction "FB_4") (pintype "input"))
    )
    (net (code "70") (name "Net-(U7-SW)") (class "Default")
      (node (ref "C6") (pin "2") (pinfunction "2_2") (pintype "passive"))
      (node (ref "L1") (pin "2") (pinfunction "2_2") (pintype "passive"))
      (node (ref "U7") (pin "2") (pinfunction "SW_2") (pintype "power_in"))
    )
    (net (code "71") (name "Net-(V1-K)") (class "Default")
      (node (ref "LED5") (pin "A") (pinfunction "A_A") (pintype "passive"))
      (node (ref "V1") (pin "C") (pinfunction "K_C") (pintype "bidirectional"))
    )
    (net (code "72") (name "unconnected-(J15-Pad3)") (class "Default")
      (node (ref "J15") (pin "3") (pinfunction "3_3") (pintype "passive"))
    )
    (net (code "73") (name "unconnected-(SV1-Pad1)") (class "Default")
      (node (ref "SV1") (pin "1") (pinfunction "1_1") (pintype "passive"))
    )
    (net (code "74") (name "unconnected-(SV1-Pad3)") (class "Default")
      (node (ref "SV1") (pin "3") (pinfunction "3_3") (pintype "passive"))
    )
    (net (code "75") (name "unconnected-(SV1-Pad5)") (class "Default")
      (node (ref "SV1") (pin "5") (pinfunction "5_5") (pintype "passive"))
    )
    (net (code "76") (name "unconnected-(SV1-Pad7)") (class "Default")
      (node (ref "SV1") (pin "7") (pinfunction "7_7") (pintype "passive"))
    )
    (net (code "77") (name "unconnected-(SV1-Pad11)") (class "Default")
      (node (ref "SV1") (pin "11") (pinfunction "11_11") (pintype "passive"))
    )
    (net (code "78") (name "unconnected-(SV1-Pad12)") (class "Default")
      (node (ref "SV1") (pin "12") (pinfunction "12_12") (pintype "passive"))
    )
    (net (code "79") (name "unconnected-(SV1-Pad13)") (class "Default")
      (node (ref "SV1") (pin "13") (pinfunction "13_13") (pintype "passive"))
    )
    (net (code "80") (name "unconnected-(SV1-Pad15)") (class "Default")
      (node (ref "SV1") (pin "15") (pinfunction "15_15") (pintype "passive"))
    )
    (net (code "81") (name "unconnected-(SV1-Pad16)") (class "Default")
      (node (ref "SV1") (pin "16") (pinfunction "16_16") (pintype "passive"))
    )
    (net (code "82") (name "unconnected-(SV1-Pad17)") (class "Default")
      (node (ref "SV1") (pin "17") (pinfunction "17_17") (pintype "passive"))
    )
    (net (code "83") (name "unconnected-(SV1-Pad18)") (class "Default")
      (node (ref "SV1") (pin "18") (pinfunction "18_18") (pintype "passive"))
    )
    (net (code "84") (name "unconnected-(SV1-Pad19)") (class "Default")
      (node (ref "SV1") (pin "19") (pinfunction "19_19") (pintype "passive"))
    )
    (net (code "85") (name "unconnected-(SV1-Pad21)") (class "Default")
      (node (ref "SV1") (pin "21") (pinfunction "21_21") (pintype "passive"))
    )
    (net (code "86") (name "unconnected-(SV1-Pad22)") (class "Default")
      (node (ref "SV1") (pin "22") (pinfunction "22_22") (pintype "passive"))
    )
    (net (code "87") (name "unconnected-(SV1-Pad23)") (class "Default")
      (node (ref "SV1") (pin "23") (pinfunction "23_23") (pintype "passive"))
    )
    (net (code "88") (name "unconnected-(SV1-Pad24)") (class "Default")
      (node (ref "SV1") (pin "24") (pinfunction "24_24") (pintype "passive"))
    )
    (net (code "89") (name "unconnected-(SV1-Pad26)") (class "Default")
      (node (ref "SV1") (pin "26") (pinfunction "26_26") (pintype "passive"))
    )
    (net (code "90") (name "unconnected-(SV1-Pad27)") (class "Default")
      (node (ref "SV1") (pin "27") (pinfunction "27_27") (pintype "passive"))
    )
    (net (code "91") (name "unconnected-(SV1-Pad28)") (class "Default")
      (node (ref "SV1") (pin "28") (pinfunction "28_28") (pintype "passive"))
    )
    (net (code "92") (name "unconnected-(SV1-Pad29)") (class "Default")
      (node (ref "SV1") (pin "29") (pinfunction "29_29") (pintype "passive"))
    )
    (net (code "93") (name "unconnected-(SV1-Pad31)") (class "Default")
      (node (ref "SV1") (pin "31") (pinfunction "31_31") (pintype "passive"))
    )
    (net (code "94") (name "unconnected-(SV1-Pad32)") (class "Default")
      (node (ref "SV1") (pin "32") (pinfunction "32_32") (pintype "passive"))
    )
    (net (code "95") (name "unconnected-(SV1-Pad33)") (class "Default")
      (node (ref "SV1") (pin "33") (pinfunction "33_33") (pintype "passive"))
    )
    (net (code "96") (name "unconnected-(SV1-Pad35)") (class "Default")
      (node (ref "SV1") (pin "35") (pinfunction "35_35") (pintype "passive"))
    )
    (net (code "97") (name "unconnected-(SV1-Pad36)") (class "Default")
      (node (ref "SV1") (pin "36") (pinfunction "36_36") (pintype "passive"))
    )
    (net (code "98") (name "unconnected-(SV1-Pad37)") (class "Default")
      (node (ref "SV1") (pin "37") (pinfunction "37_37") (pintype "passive"))
    )
    (net (code "99") (name "unconnected-(SV1-Pad38)") (class "Default")
      (node (ref "SV1") (pin "38") (pinfunction "38_38") (pintype "passive"))
    )
    (net (code "100") (name "unconnected-(SV1-Pad40)") (class "Default")
      (node (ref "SV1") (pin "40") (pinfunction "40_40") (pintype "passive"))
    )
    (net (code "101") (name "unconnected-(SV5-Pad3)") (class "Default")
      (node (ref "SV5") (pin "3") (pinfunction "3_3") (pintype "passive"))
    )
    (net (code "102") (name "unconnected-(SV5-Pad21)") (class "Default")
      (node (ref "SV5") (pin "21") (pinfunction "21_21") (pintype "passive"))
    )
    (net (code "103") (name "unconnected-(SV5-Pad22)") (class "Default")
      (node (ref "SV5") (pin "22") (pinfunction "22_22") (pintype "passive"))
    )
    (net (code "104") (name "unconnected-(SV5-Pad23)") (class "Default")
      (node (ref "SV5") (pin "23") (pinfunction "23_23") (pintype "passive"))
    )
    (net (code "105") (name "unconnected-(U$5-3V3(OUT)-Pad36)") (class "Default")
      (node (ref "U$5") (pin "36") (pinfunction "3V3(OUT)_36") (pintype "output"))
    )
    (net (code "106") (name "unconnected-(U$5-RUN-Pad30)") (class "Default")
      (node (ref "U$5") (pin "30") (pinfunction "RUN_30") (pintype "passive"))
    )
    (net (code "107") (name "unconnected-(U7-EN-Pad5)") (class "Default")
      (node (ref "U7") (pin "5") (pinfunction "EN_5") (pintype "input"))
    )
  )
)
